# H-Bridge_-_DRV8829.net
KiCad netlist of a schematic drawn in Altium Designer
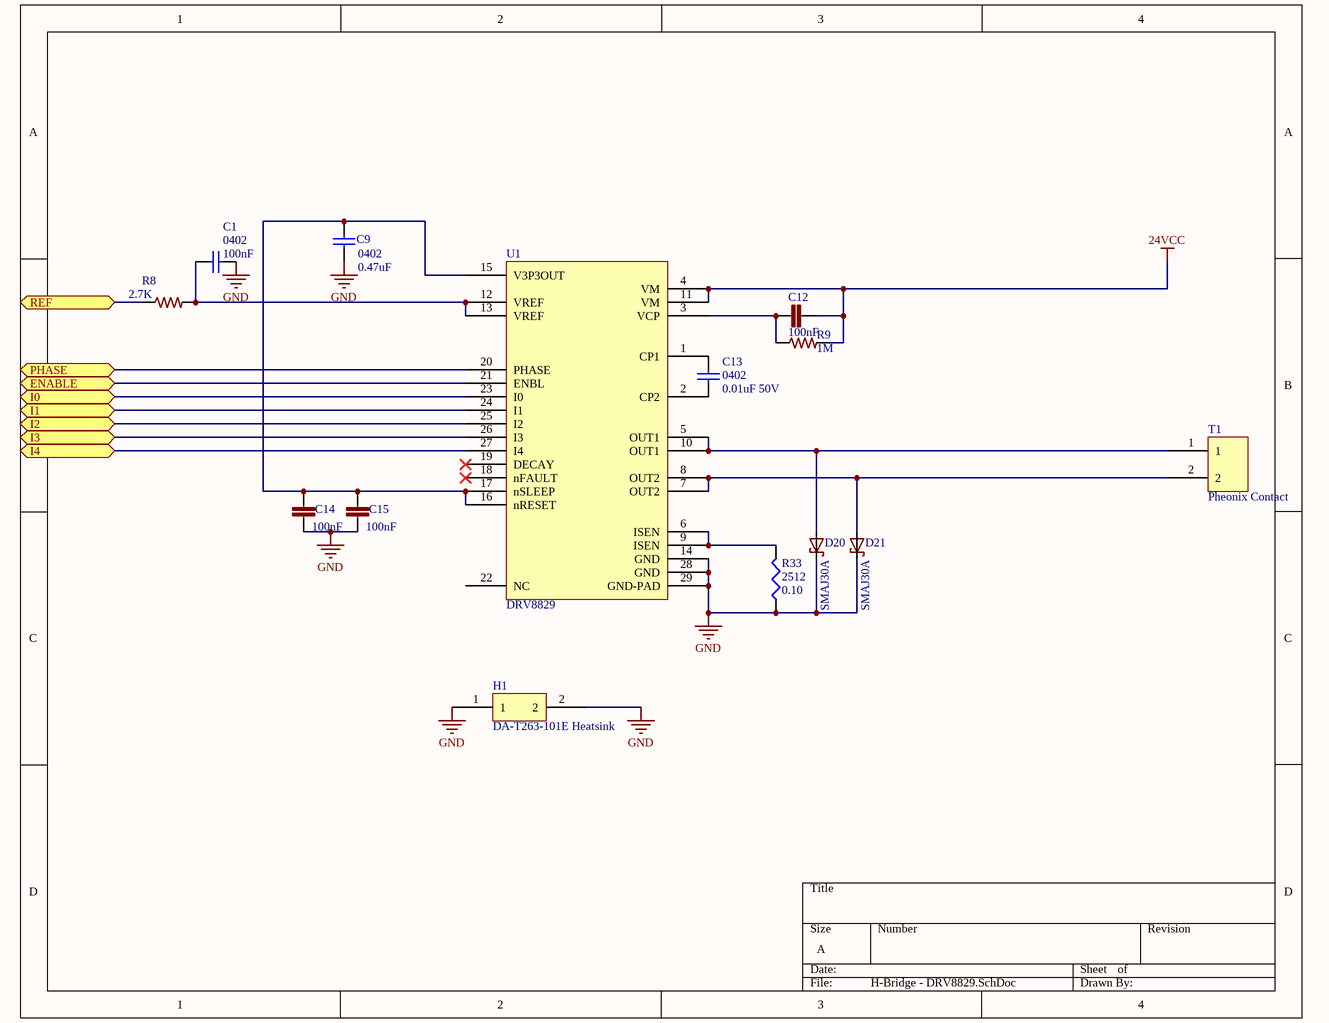
[diagram p0: H-Bridge - DRV8829.SchDoc]

(export (version "E")
  (design (tool "Eeschema 10.0.6"))
  (components
    (comp (ref "C1")
      (value "100nF")
      (footprint "C0402")
      (description "Capacitor (Semiconductor SIM Model)")
      (fields
        (field (name "MFR PART #") "GRM155R71C104KA88D")
        (field (name "MFR") "Murata")
        (field (name "PACKAGEREFERENCE") "0402")
        (field (name "PUBLISHER") "Ultimachine")
      )
      (libsource (lib "Tigershark3D") (part "100nF C0402 - GRM155R71C104KA88D"))
    )
    (comp (ref "C9")
      (value "0.47uF")
      (footprint "C0402")
      (description "0.47uF 6.3v C0402 - GRM155R60J474KE19D")
      (fields
        (field (name "MFR PART #") "GRM155R60J474KE19D")
        (field (name "MFR") "Murata")
        (field (name "PACKAGEREFERENCE") "0402")
        (field (name "PUBLISHER") "Ultimachine")
      )
      (libsource (lib "Tigershark3D") (part "GRM155R60J474KE19D"))
    )
    (comp (ref "C12")
      (value "100nF")
      (footprint "C0603")
      (description "CAP CER 0603 100nF 50V 10% X7R")
      (fields
        (field (name "MANUFACTURERPARTNUMBER") "C0603C104K5RACTU")
        (field (name "PUBLISHER") "UltiMachine")
      )
      (libsource (lib "3Delight") (part "C0603C104K5RACTU"))
    )
    (comp (ref "C13")
      (value "0.01uF 50V")
      (footprint "C0402")
      (description "CAP CER 10000PF 50V X7R 0402")
      (fields
        (field (name "MFR PART #") "GRM155R71H103JA88D")
        (field (name "MFR") "Murata")
        (field (name "PACKAGEREFERENCE") "0402")
        (field (name "PUBLISHER") "Ultimachine")
      )
      (libsource (lib "Tigershark3D") (part "GRM155R71H103JA88D"))
    )
    (comp (ref "C14")
      (value "100nF")
      (footprint "C0402")
      (description "CAP CER 0402 100nF 16V 10% X7R")
      (fields
        (field (name "MANUFACTURERPARTNUMBER") "GRM155R71C104KA88D")
        (field (name "PUBLISHER") "UltiMachine")
      )
      (libsource (lib "3Delight") (part "GRM155R71C104KA88D"))
    )
    (comp (ref "C15")
      (value "100nF")
      (footprint "C0402")
      (description "CAP CER 0402 100nF 16V 10% X7R")
      (fields
        (field (name "MANUFACTURERPARTNUMBER") "GRM155R71C104KA88D")
        (field (name "PUBLISHER") "UltiMachine")
      )
      (libsource (lib "3Delight") (part "GRM155R71C104KA88D"))
    )
    (comp (ref "D20")
      (value "SMAJ30A")
      (footprint "SMA-SM")
      (description "DIODE TVS 30V SMA")
      (fields (field (name "PUBLISHER") "UltiMachine"))
      (libsource (lib "Tigershark3D") (part "SMAJ30A"))
    )
    (comp (ref "D21")
      (value "SMAJ30A")
      (footprint "SMA-SM")
      (description "DIODE TVS 30V SMA")
      (fields (field (name "PUBLISHER") "UltiMachine"))
      (libsource (lib "Tigershark3D") (part "SMAJ30A"))
    )
    (comp (ref "H1")
      (value "DA-T263-101E Heatsink")
      (footprint "DA-T263-101E")
      (libsource (lib "MongoosMini") (part "DA-T263-101E Heatsink"))
    )
    (comp (ref "R8")
      (value "2.7K")
      (footprint "R0402")
      (description "RES SMD 2.7K OHM 1% 1/10W 0402")
      (fields
        (field (name "MANUFACTURER") "Panasonic")
        (field (name "MANUFACTURERPARTNUMBER") "ERJ2GEJ105X")
        (field (name "PUBLISHER") "Adam")
      )
      (libsource (lib "Tigershark3D") (part "ERJ-2RKF2701X"))
    )
    (comp (ref "R9")
      (value "1M")
      (footprint "R0402")
      (description "RES 0402 1M 100mW 5%")
      (fields (field (name "MANUFACTURERPARTNUMBER") "ERJ2GEJ105X") (field (name "PUBLISHER") "UltiMachine"))
      (libsource (lib "Tigershark3D") (part "ERJ2GEJ105X"))
    )
    (comp (ref "R33")
      (value "2512")
      (footprint "2512R-0.55")
      (description "RES SMD 0.1 OHM 1% 2W 2512")
      (fields (field (name "MFR") "Stackpole ELectronics Inc") (field (name "ALTIUM_VALUE") "0.10"))
      (libsource (lib "Tigershark3D") (part "CSRN2512FTR100"))
    )
    (comp (ref "T1")
      (value "Pheonix Contact")
      (footprint "CON-PHEONIX-508-Alt")
      (libsource (lib "Ribbon Breakout Schem Symbols") (part "Pheonix Contact 2X1"))
    )
    (comp (ref "U1")
      (value "DRV8829")
      (footprint "TSSOP28-DRV8829")
      (description "IC MOTOR DRIVER PAR 28HTSSOP")
      (fields (field (name "MFR") "Texas Instruments"))
      (libsource (lib "MongoosMini") (part "DRV8829"))
    )
  )
  (nets
    (net (code "1") (name "/ENABLE") (class "Default")
      (node (ref "U1") (pin "21") (pinfunction "ENBL_21") (pintype "passive"))
    )
    (net (code "2") (name "/I0") (class "Default")
      (node (ref "U1") (pin "23") (pinfunction "I0_23") (pintype "passive"))
    )
    (net (code "3") (name "/I1") (class "Default")
      (node (ref "U1") (pin "24") (pinfunction "I1_24") (pintype "passive"))
    )
    (net (code "4") (name "/I2") (class "Default")
      (node (ref "U1") (pin "25") (pinfunction "I2_25") (pintype "passive"))
    )
    (net (code "5") (name "/I3") (class "Default")
      (node (ref "U1") (pin "26") (pinfunction "I3_26") (pintype "passive"))
    )
    (net (code "6") (name "/I4") (class "Default")
      (node (ref "U1") (pin "27") (pinfunction "I4_27") (pintype "passive"))
    )
    (net (code "7") (name "/PHASE") (class "Default")
      (node (ref "U1") (pin "20") (pinfunction "PHASE_20") (pintype "passive"))
    )
    (net (code "8") (name "/REF") (class "Default")
      (node (ref "R8") (pin "1") (pinfunction "1_1") (pintype "passive"))
    )
    (net (code "9") (name "24VCC") (class "Default")
      (node (ref "C12") (pin "2") (pinfunction "2_2") (pintype "passive"))
      (node (ref "R9") (pin "2") (pinfunction "2_2") (pintype "passive"))
      (node (ref "U1") (pin "11") (pinfunction "VM_11") (pintype "passive"))
      (node (ref "U1") (pin "4") (pinfunction "VM_4") (pintype "passive"))
    )
    (net (code "10") (name "GND") (class "Default")
      (node (ref "C1") (pin "1") (pinfunction "1_1") (pintype "passive"))
      (node (ref "C14") (pin "2") (pinfunction "2_2") (pintype "passive"))
      (node (ref "C15") (pin "2") (pinfunction "2_2") (pintype "passive"))
      (node (ref "C9") (pin "1") (pinfunction "1_1") (pintype "passive"))
      (node (ref "D20") (pin "C") (pinfunction "C_C") (pintype "passive"))
      (node (ref "D21") (pin "C") (pinfunction "C_C") (pintype "passive"))
      (node (ref "H1") (pin "1") (pinfunction "1_1") (pintype "passive"))
      (node (ref "H1") (pin "2") (pinfunction "2_2") (pintype "passive"))
      (node (ref "R33") (pin "1") (pinfunction "1_1") (pintype "passive"))
      (node (ref "U1") (pin "14") (pinfunction "GND_14") (pintype "passive"))
      (node (ref "U1") (pin "28") (pinfunction "GND_28") (pintype "passive"))
      (node (ref "U1") (pin "29") (pinfunction "GND-PAD_29") (pintype "passive"))
    )
    (net (code "11") (name "Net-(C1-Pad2)") (class "Default")
      (node (ref "C1") (pin "2") (pinfunction "2_2") (pintype "passive"))
      (node (ref "R8") (pin "2") (pinfunction "2_2") (pintype "passive"))
      (node (ref "U1") (pin "12") (pinfunction "VREF_12") (pintype "passive"))
      (node (ref "U1") (pin "13") (pinfunction "VREF_13") (pintype "passive"))
    )
    (net (code "12") (name "Net-(D20-PadA)") (class "Default")
      (node (ref "D20") (pin "A") (pinfunction "A_A") (pintype "passive"))
      (node (ref "T1") (pin "1") (pinfunction "1_1") (pintype "passive"))
      (node (ref "U1") (pin "10") (pinfunction "OUT1_10") (pintype "passive"))
      (node (ref "U1") (pin "5") (pinfunction "OUT1_5") (pintype "passive"))
    )
    (net (code "13") (name "Net-(D21-PadA)") (class "Default")
      (node (ref "D21") (pin "A") (pinfunction "A_A") (pintype "passive"))
      (node (ref "T1") (pin "2") (pinfunction "2_2") (pintype "passive"))
      (node (ref "U1") (pin "7") (pinfunction "OUT2_7") (pintype "passive"))
      (node (ref "U1") (pin "8") (pinfunction "OUT2_8") (pintype "passive"))
    )
    (net (code "14") (name "Net-(R33-Pad2)") (class "Default")
      (node (ref "R33") (pin "2") (pinfunction "2_2") (pintype "passive"))
      (node (ref "U1") (pin "6") (pinfunction "ISEN_6") (pintype "passive"))
      (node (ref "U1") (pin "9") (pinfunction "ISEN_9") (pintype "passive"))
    )
    (net (code "15") (name "Net-(U1-CP1)") (class "Default")
      (node (ref "C13") (pin "2") (pinfunction "2_2") (pintype "passive"))
      (node (ref "U1") (pin "1") (pinfunction "CP1_1") (pintype "passive"))
    )
    (net (code "16") (name "Net-(U1-CP2)") (class "Default")
      (node (ref "C13") (pin "1") (pinfunction "1_1") (pintype "passive"))
      (node (ref "U1") (pin "2") (pinfunction "CP2_2") (pintype "passive"))
    )
    (net (code "17") (name "Net-(U1-V3P3OUT)") (class "Default")
      (node (ref "C14") (pin "1") (pinfunction "1_1") (pintype "passive"))
      (node (ref "C15") (pin "1") (pinfunction "1_1") (pintype "passive"))
      (node (ref "C9") (pin "2") (pinfunction "2_2") (pintype "passive"))
      (node (ref "U1") (pin "15") (pinfunction "V3P3OUT_15") (pintype "passive"))
      (node (ref "U1") (pin "16") (pinfunction "nRESET_16") (pintype "passive"))
      (node (ref "U1") (pin "17") (pinfunction "nSLEEP_17") (pintype "passive"))
    )
    (net (code "18") (name "Net-(U1-VCP)") (class "Default")
      (node (ref "C12") (pin "1") (pinfunction "1_1") (pintype "passive"))
      (node (ref "R9") (pin "1") (pinfunction "1_1") (pintype "passive"))
      (node (ref "U1") (pin "3") (pinfunction "VCP_3") (pintype "passive"))
    )
    (net (code "19") (name "unconnected-(U1-DECAY-Pad19)") (class "Default")
      (node (ref "U1") (pin "19") (pinfunction "DECAY_19") (pintype "passive+no_connect"))
    )
    (net (code "20") (name "unconnected-(U1-NC-Pad22)") (class "Default")
      (node (ref "U1") (pin "22") (pinfunction "NC_22") (pintype "passive"))
    )
    (net (code "21") (name "unconnected-(U1-nFAULT-Pad18)") (class "Default")
      (node (ref "U1") (pin "18") (pinfunction "nFAULT_18") (pintype "passive+no_connect"))
    )
  )
)
